# prot_PBC.net
KiCad netlist of a schematic drawn in EAGLE
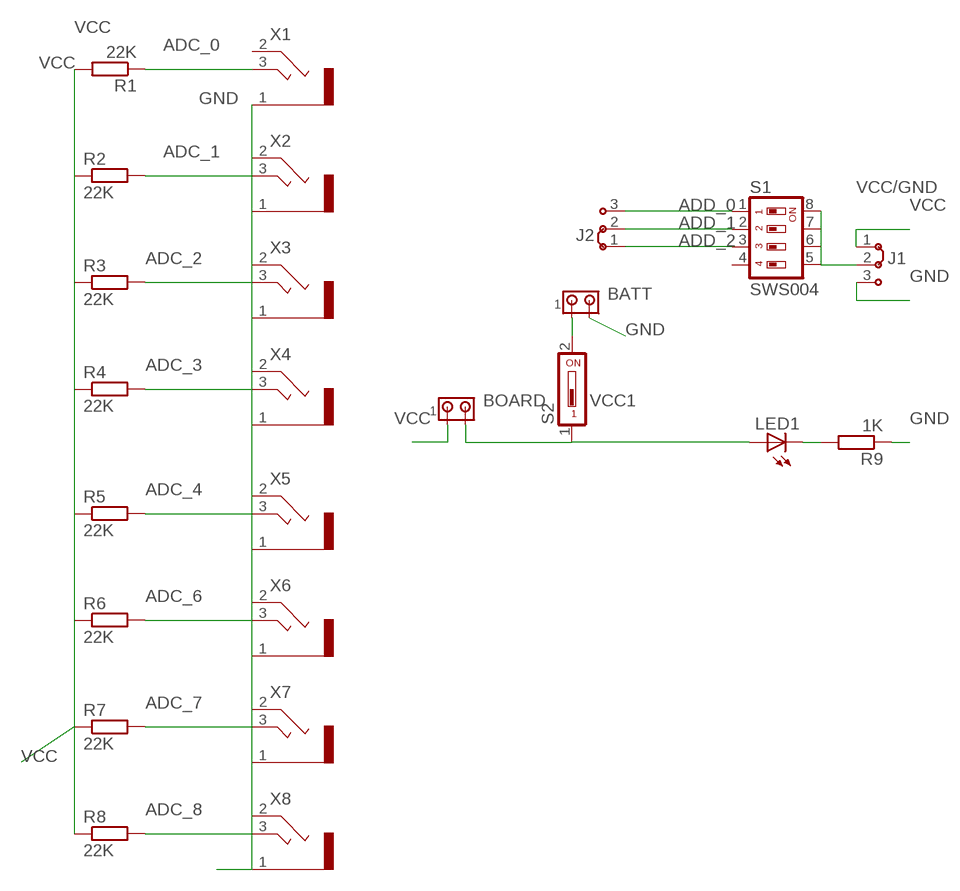
[diagram p0: schematic, sheet 1]

(export (version "E")
  (design (tool "Eeschema 10.0.6"))
  (components
    (comp (ref "BATT")
      (value "MTA02-156")
      (footprint "eagle-import:1X2MTA")
      (libsource (lib "eagle-import") (part "MTA02-156"))
    )
    (comp (ref "BOARD")
      (value "MTA02-156")
      (footprint "eagle-import:1X2MTA")
      (libsource (lib "eagle-import") (part "MTA02-156"))
    )
    (comp (ref "J1")
      (value "J2X2MM")
      (footprint "eagle-import:04C")
      (libsource (lib "eagle-import") (part "J2X2MM"))
    )
    (comp (ref "J2")
      (value "J2X2MM")
      (footprint "eagle-import:04C")
      (libsource (lib "eagle-import") (part "J2X2MM"))
    )
    (comp (ref "LED1")
      (value "LED5MM")
      (footprint "eagle-import:LED5MM")
      (libsource (lib "eagle-import") (part "LED5MM"))
    )
    (comp (ref "R1")
      (value "22K")
      (footprint "eagle-import:0207_7")
      (libsource (lib "eagle-import") (part "R-EU_0207/7"))
    )
    (comp (ref "R2")
      (value "22K")
      (footprint "eagle-import:0207_7")
      (libsource (lib "eagle-import") (part "R-EU_0207/7"))
    )
    (comp (ref "R3")
      (value "22K")
      (footprint "eagle-import:0207_7")
      (libsource (lib "eagle-import") (part "R-EU_0207/7"))
    )
    (comp (ref "R4")
      (value "22K")
      (footprint "eagle-import:0207_7")
      (libsource (lib "eagle-import") (part "R-EU_0207/7"))
    )
    (comp (ref "R5")
      (value "22K")
      (footprint "eagle-import:0207_7")
      (libsource (lib "eagle-import") (part "R-EU_0207/7"))
    )
    (comp (ref "R6")
      (value "22K")
      (footprint "eagle-import:0207_7")
      (libsource (lib "eagle-import") (part "R-EU_0207/7"))
    )
    (comp (ref "R7")
      (value "22K")
      (footprint "eagle-import:0207_7")
      (libsource (lib "eagle-import") (part "R-EU_0207/7"))
    )
    (comp (ref "R8")
      (value "22K")
      (footprint "eagle-import:0207_7")
      (libsource (lib "eagle-import") (part "R-EU_0207/7"))
    )
    (comp (ref "R9")
      (value "1K")
      (footprint "eagle-import:0207_7")
      (libsource (lib "eagle-import") (part "R-EU_0207/7"))
    )
    (comp (ref "S1")
      (value "SWS004")
      (footprint "eagle-import:SMS-004")
      (libsource (lib "eagle-import") (part "SWS004"))
    )
    (comp (ref "S2")
      (value "DS01")
      (footprint "eagle-import:DS-01")
      (libsource (lib "eagle-import") (part "DS01"))
    )
    (comp (ref "X1")
      (value "1501_03")
      (footprint "eagle-import:1501_03")
      (libsource (lib "eagle-import") (part "1501_03"))
    )
    (comp (ref "X2")
      (value "1501_03")
      (footprint "eagle-import:1501_03")
      (libsource (lib "eagle-import") (part "1501_03"))
    )
    (comp (ref "X3")
      (value "1501_03")
      (footprint "eagle-import:1501_03")
      (libsource (lib "eagle-import") (part "1501_03"))
    )
    (comp (ref "X4")
      (value "1501_03")
      (footprint "eagle-import:1501_03")
      (libsource (lib "eagle-import") (part "1501_03"))
    )
    (comp (ref "X5")
      (value "1501_03")
      (footprint "eagle-import:1501_03")
      (libsource (lib "eagle-import") (part "1501_03"))
    )
    (comp (ref "X6")
      (value "1501_03")
      (footprint "eagle-import:1501_03")
      (libsource (lib "eagle-import") (part "1501_03"))
    )
    (comp (ref "X7")
      (value "1501_03")
      (footprint "eagle-import:1501_03")
      (libsource (lib "eagle-import") (part "1501_03"))
    )
    (comp (ref "X8")
      (value "1501_03")
      (footprint "eagle-import:1501_03")
      (libsource (lib "eagle-import") (part "1501_03"))
    )
  )
  (nets
    (net (code "1") (name "/ADC_0") (class "Default")
      (node (ref "R1") (pin "1") (pinfunction "1_1") (pintype "passive"))
      (node (ref "X1") (pin "3") (pinfunction "3_3") (pintype "passive"))
    )
    (net (code "2") (name "/ADC_1") (class "Default")
      (node (ref "R2") (pin "2") (pinfunction "2_2") (pintype "passive"))
      (node (ref "X2") (pin "3") (pinfunction "3_3") (pintype "passive"))
    )
    (net (code "3") (name "/ADC_2") (class "Default")
      (node (ref "R3") (pin "2") (pinfunction "2_2") (pintype "passive"))
      (node (ref "X3") (pin "3") (pinfunction "3_3") (pintype "passive"))
    )
    (net (code "4") (name "/ADC_3") (class "Default")
      (node (ref "R4") (pin "2") (pinfunction "2_2") (pintype "passive"))
      (node (ref "X4") (pin "3") (pinfunction "3_3") (pintype "passive"))
    )
    (net (code "5") (name "/ADC_4") (class "Default")
      (node (ref "R5") (pin "2") (pinfunction "2_2") (pintype "passive"))
      (node (ref "X5") (pin "3") (pinfunction "3_3") (pintype "passive"))
    )
    (net (code "6") (name "/ADC_6") (class "Default")
      (node (ref "R6") (pin "2") (pinfunction "2_2") (pintype "passive"))
      (node (ref "X6") (pin "3") (pinfunction "3_3") (pintype "passive"))
    )
    (net (code "7") (name "/ADC_7") (class "Default")
      (node (ref "R7") (pin "2") (pinfunction "2_2") (pintype "passive"))
      (node (ref "X7") (pin "3") (pinfunction "3_3") (pintype "passive"))
    )
    (net (code "8") (name "/ADC_8") (class "Default")
      (node (ref "R8") (pin "2") (pinfunction "2_2") (pintype "passive"))
      (node (ref "X8") (pin "3") (pinfunction "3_3") (pintype "passive"))
    )
    (net (code "9") (name "/ADD_0") (class "Default")
      (node (ref "J2") (pin "3") (pinfunction "3_3") (pintype "passive"))
      (node (ref "S1") (pin "1") (pinfunction "1_1") (pintype "passive"))
    )
    (net (code "10") (name "/ADD_1") (class "Default")
      (node (ref "J2") (pin "2") (pinfunction "2_2") (pintype "passive"))
      (node (ref "S1") (pin "2") (pinfunction "2_2") (pintype "passive"))
    )
    (net (code "11") (name "/ADD_2") (class "Default")
      (node (ref "J2") (pin "1") (pinfunction "1_1") (pintype "passive"))
      (node (ref "S1") (pin "3") (pinfunction "3_3") (pintype "passive"))
    )
    (net (code "12") (name "/GND") (class "Default")
      (node (ref "BATT") (pin "2") (pinfunction "2_2") (pintype "passive"))
      (node (ref "J1") (pin "3") (pinfunction "3_3") (pintype "passive"))
      (node (ref "R9") (pin "1") (pinfunction "1_1") (pintype "passive"))
      (node (ref "X1") (pin "1") (pinfunction "1_1") (pintype "passive"))
      (node (ref "X2") (pin "1") (pinfunction "1_1") (pintype "passive"))
      (node (ref "X3") (pin "1") (pinfunction "1_1") (pintype "passive"))
      (node (ref "X4") (pin "1") (pinfunction "1_1") (pintype "passive"))
      (node (ref "X5") (pin "1") (pinfunction "1_1") (pintype "passive"))
      (node (ref "X6") (pin "1") (pinfunction "1_1") (pintype "passive"))
      (node (ref "X7") (pin "1") (pinfunction "1_1") (pintype "passive"))
      (node (ref "X8") (pin "1") (pinfunction "1_1") (pintype "passive"))
    )
    (net (code "13") (name "/VCC") (class "Default")
      (node (ref "BOARD") (pin "1") (pinfunction "1_1") (pintype "passive"))
      (node (ref "J1") (pin "1") (pinfunction "1_1") (pintype "passive"))
      (node (ref "R1") (pin "2") (pinfunction "2_2") (pintype "passive"))
      (node (ref "R2") (pin "1") (pinfunction "1_1") (pintype "passive"))
      (node (ref "R3") (pin "1") (pinfunction "1_1") (pintype "passive"))
      (node (ref "R4") (pin "1") (pinfunction "1_1") (pintype "passive"))
      (node (ref "R5") (pin "1") (pinfunction "1_1") (pintype "passive"))
      (node (ref "R6") (pin "1") (pinfunction "1_1") (pintype "passive"))
      (node (ref "R7") (pin "1") (pinfunction "1_1") (pintype "passive"))
      (node (ref "R8") (pin "1") (pinfunction "1_1") (pintype "passive"))
    )
    (net (code "14") (name "/VCC1") (class "Default")
      (node (ref "BOARD") (pin "2") (pinfunction "2_2") (pintype "passive"))
      (node (ref "LED1") (pin "A") (pinfunction "A_A") (pintype "passive"))
      (node (ref "S2") (pin "1") (pinfunction "1_1") (pintype "passive"))
    )
    (net (code "15") (name "/VCC{slash}GND") (class "Default")
      (node (ref "J1") (pin "2") (pinfunction "2_2") (pintype "passive"))
      (node (ref "S1") (pin "5") (pinfunction "5_5") (pintype "passive"))
      (node (ref "S1") (pin "6") (pinfunction "6_6") (pintype "passive"))
      (node (ref "S1") (pin "7") (pinfunction "7_7") (pintype "passive"))
      (node (ref "S1") (pin "8") (pinfunction "8_8") (pintype "passive"))
    )
    (net (code "16") (name "Net-(BATT-Pad1)") (class "Default")
      (node (ref "BATT") (pin "1") (pinfunction "1_1") (pintype "passive"))
      (node (ref "S2") (pin "2") (pinfunction "2_2") (pintype "passive"))
    )
    (net (code "17") (name "Net-(LED1-C)") (class "Default")
      (node (ref "LED1") (pin "K") (pinfunction "C_K") (pintype "passive"))
      (node (ref "R9") (pin "2") (pinfunction "2_2") (pintype "passive"))
    )
    (net (code "18") (name "unconnected-(S1-Pad4)") (class "Default")
      (node (ref "S1") (pin "4") (pinfunction "4_4") (pintype "passive"))
    )
    (net (code "19") (name "unconnected-(X1-Pad2)") (class "Default")
      (node (ref "X1") (pin "2") (pinfunction "2_2") (pintype "passive"))
    )
    (net (code "20") (name "unconnected-(X2-Pad2)") (class "Default")
      (node (ref "X2") (pin "2") (pinfunction "2_2") (pintype "passive"))
    )
    (net (code "21") (name "unconnected-(X3-Pad2)") (class "Default")
      (node (ref "X3") (pin "2") (pinfunction "2_2") (pintype "passive"))
    )
    (net (code "22") (name "unconnected-(X4-Pad2)") (class "Default")
      (node (ref "X4") (pin "2") (pinfunction "2_2") (pintype "passive"))
    )
    (net (code "23") (name "unconnected-(X5-Pad2)") (class "Default")
      (node (ref "X5") (pin "2") (pinfunction "2_2") (pintype "passive"))
    )
    (net (code "24") (name "unconnected-(X6-Pad2)") (class "Default")
      (node (ref "X6") (pin "2") (pinfunction "2_2") (pintype "passive"))
    )
    (net (code "25") (name "unconnected-(X7-Pad2)") (class "Default")
      (node (ref "X7") (pin "2") (pinfunction "2_2") (pintype "passive"))
    )
    (net (code "26") (name "unconnected-(X8-Pad2)") (class "Default")
      (node (ref "X8") (pin "2") (pinfunction "2_2") (pintype "passive"))
    )
  )
)
